# ARM2toARM6Adapter.net
KiCad netlist of a schematic drawn in Altium Designer
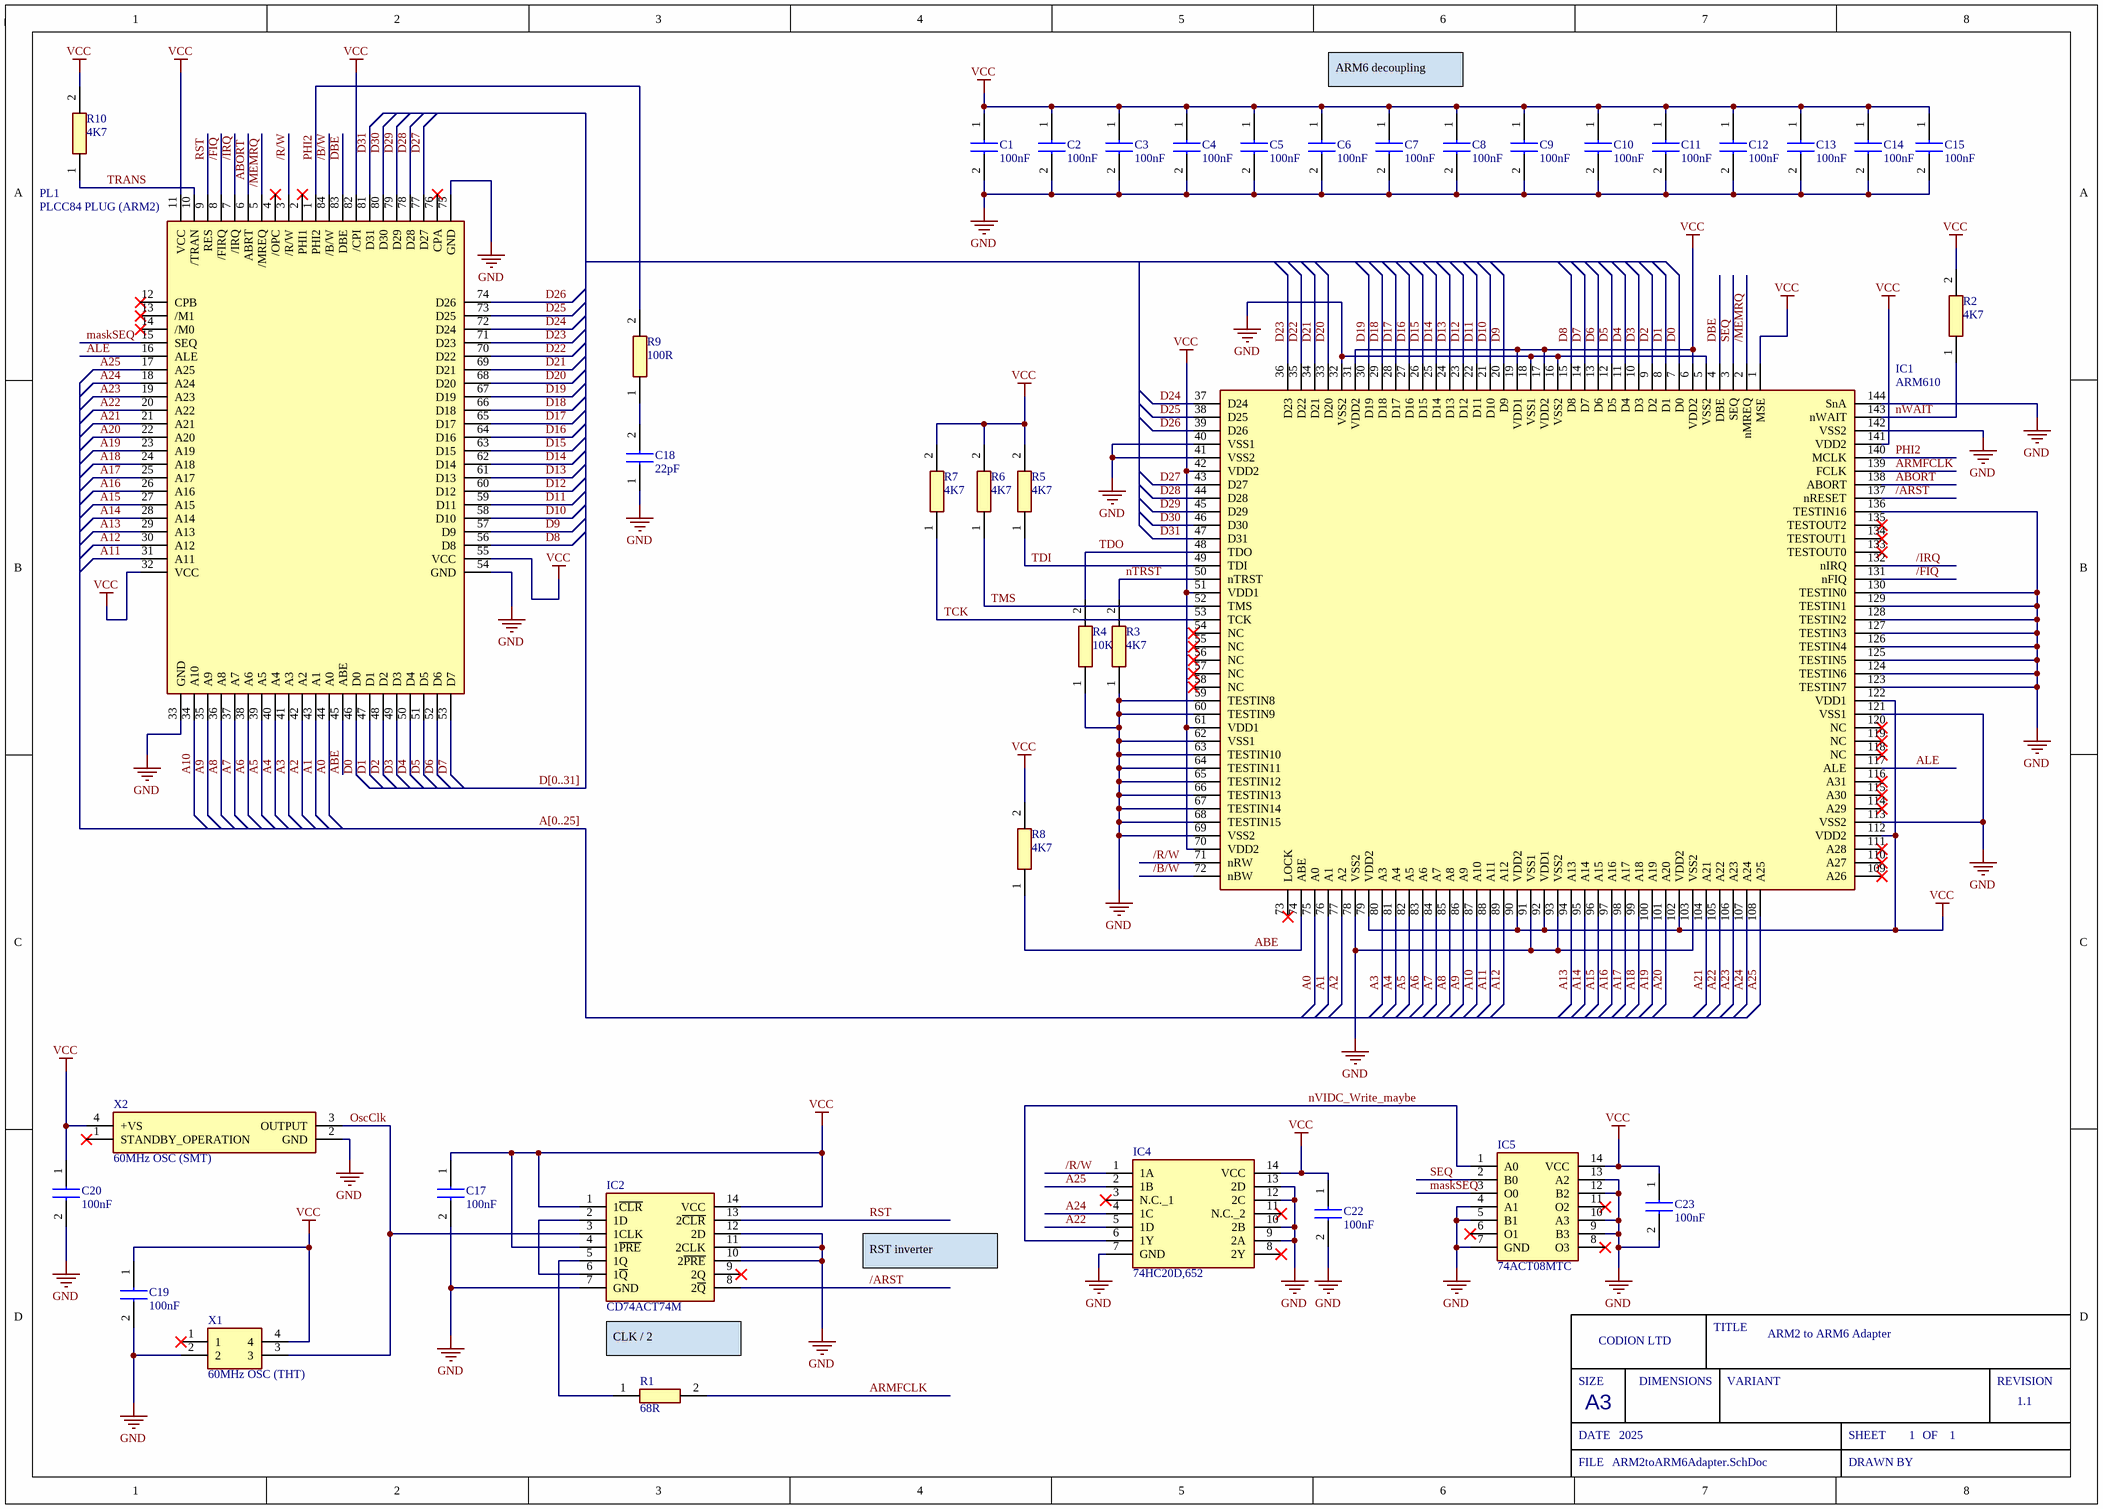
[diagram p0: ARM2toARM6Adapter.SchDoc]

(export (version "E")
  (design (tool "Eeschema 10.0.6"))
  (components
    (comp (ref "C1")
      (value "100nF")
      (footprint "SamacSys:CAPC2012X145N")
      (description "Capacitor")
      (fields
        (field (name "MANUFACTURER_PART_NUMBER") "C2012X7R1H104K125AM")
        (field (name "MOUSER PART NUMBER") "810-C2012X7R1H104KT5")
      )
      (libsource (lib "*") (part "C2012X7R1H104K125AM"))
    )
    (comp (ref "C2")
      (value "100nF")
      (footprint "SamacSys:CAPC2012X145N")
      (description "Capacitor")
      (fields
        (field (name "MANUFACTURER_PART_NUMBER") "C2012X7R1H104K125AM")
        (field (name "MOUSER PART NUMBER") "810-C2012X7R1H104KT5")
      )
      (libsource (lib "*") (part "C2012X7R1H104K125AM"))
    )
    (comp (ref "C3")
      (value "100nF")
      (footprint "SamacSys:CAPC2012X145N")
      (description "Capacitor")
      (fields
        (field (name "MANUFACTURER_PART_NUMBER") "C2012X7R1H104K125AM")
        (field (name "MOUSER PART NUMBER") "810-C2012X7R1H104KT5")
      )
      (libsource (lib "*") (part "C2012X7R1H104K125AM"))
    )
    (comp (ref "C4")
      (value "100nF")
      (footprint "SamacSys:CAPC2012X145N")
      (description "Capacitor")
      (fields
        (field (name "MANUFACTURER_PART_NUMBER") "C2012X7R1H104K125AM")
        (field (name "MOUSER PART NUMBER") "810-C2012X7R1H104KT5")
      )
      (libsource (lib "*") (part "C2012X7R1H104K125AM"))
    )
    (comp (ref "C5")
      (value "100nF")
      (footprint "SamacSys:CAPC2012X145N")
      (description "Capacitor")
      (fields
        (field (name "MANUFACTURER_PART_NUMBER") "C2012X7R1H104K125AM")
        (field (name "MOUSER PART NUMBER") "810-C2012X7R1H104KT5")
      )
      (libsource (lib "*") (part "C2012X7R1H104K125AM"))
    )
    (comp (ref "C6")
      (value "100nF")
      (footprint "SamacSys:CAPC2012X145N")
      (description "Capacitor")
      (fields
        (field (name "MANUFACTURER_PART_NUMBER") "C2012X7R1H104K125AM")
        (field (name "MOUSER PART NUMBER") "810-C2012X7R1H104KT5")
      )
      (libsource (lib "*") (part "C2012X7R1H104K125AM"))
    )
    (comp (ref "C7")
      (value "100nF")
      (footprint "SamacSys:CAPC2012X145N")
      (description "Capacitor")
      (fields
        (field (name "MANUFACTURER_PART_NUMBER") "C2012X7R1H104K125AM")
        (field (name "MOUSER PART NUMBER") "810-C2012X7R1H104KT5")
      )
      (libsource (lib "*") (part "C2012X7R1H104K125AM"))
    )
    (comp (ref "C8")
      (value "100nF")
      (footprint "SamacSys:CAPC2012X145N")
      (description "Capacitor")
      (fields
        (field (name "MANUFACTURER_PART_NUMBER") "C2012X7R1H104K125AM")
        (field (name "MOUSER PART NUMBER") "810-C2012X7R1H104KT5")
      )
      (libsource (lib "*") (part "C2012X7R1H104K125AM"))
    )
    (comp (ref "C9")
      (value "100nF")
      (footprint "SamacSys:CAPC2012X145N")
      (description "Capacitor")
      (fields
        (field (name "MANUFACTURER_PART_NUMBER") "C2012X7R1H104K125AM")
        (field (name "MOUSER PART NUMBER") "810-C2012X7R1H104KT5")
      )
      (libsource (lib "*") (part "C2012X7R1H104K125AM"))
    )
    (comp (ref "C10")
      (value "100nF")
      (footprint "SamacSys:CAPC2012X145N")
      (description "Capacitor")
      (fields
        (field (name "MANUFACTURER_PART_NUMBER") "C2012X7R1H104K125AM")
        (field (name "MOUSER PART NUMBER") "810-C2012X7R1H104KT5")
      )
      (libsource (lib "*") (part "C2012X7R1H104K125AM"))
    )
    (comp (ref "C11")
      (value "100nF")
      (footprint "SamacSys:CAPC2012X145N")
      (description "Capacitor")
      (fields
        (field (name "MANUFACTURER_PART_NUMBER") "C2012X7R1H104K125AM")
        (field (name "MOUSER PART NUMBER") "810-C2012X7R1H104KT5")
      )
      (libsource (lib "*") (part "C2012X7R1H104K125AM"))
    )
    (comp (ref "C12")
      (value "100nF")
      (footprint "SamacSys:CAPC2012X145N")
      (description "Capacitor")
      (fields
        (field (name "MANUFACTURER_PART_NUMBER") "C2012X7R1H104K125AM")
        (field (name "MOUSER PART NUMBER") "810-C2012X7R1H104KT5")
      )
      (libsource (lib "*") (part "C2012X7R1H104K125AM"))
    )
    (comp (ref "C13")
      (value "100nF")
      (footprint "SamacSys:CAPC2012X145N")
      (description "Capacitor")
      (fields
        (field (name "MANUFACTURER_PART_NUMBER") "C2012X7R1H104K125AM")
        (field (name "MOUSER PART NUMBER") "810-C2012X7R1H104KT5")
      )
      (libsource (lib "*") (part "C2012X7R1H104K125AM"))
    )
    (comp (ref "C14")
      (value "100nF")
      (footprint "SamacSys:CAPC2012X145N")
      (description "Capacitor")
      (fields
        (field (name "MANUFACTURER_PART_NUMBER") "C2012X7R1H104K125AM")
        (field (name "MOUSER PART NUMBER") "810-C2012X7R1H104KT5")
      )
      (libsource (lib "*") (part "C2012X7R1H104K125AM"))
    )
    (comp (ref "C15")
      (value "100nF")
      (footprint "SamacSys:CAPC2012X145N")
      (description "Capacitor")
      (fields
        (field (name "MANUFACTURER_PART_NUMBER") "C2012X7R1H104K125AM")
        (field (name "MOUSER PART NUMBER") "810-C2012X7R1H104KT5")
      )
      (libsource (lib "*") (part "C2012X7R1H104K125AM"))
    )
    (comp (ref "C17")
      (value "100nF")
      (footprint "SamacSys:CAPC2012X145N")
      (description "Capacitor")
      (fields
        (field (name "MANUFACTURER_PART_NUMBER") "C2012X7R1H104K125AM")
        (field (name "MOUSER PART NUMBER") "810-C2012X7R1H104KT5")
      )
      (libsource (lib "*") (part "C2012X7R1H104K125AM"))
    )
    (comp (ref "C18")
      (value "22pF")
      (footprint "SamacSys:CAPC1608X90N")
      (description "Capacitor")
      (fields
        (field (name "MANUFACTURER_PART_NUMBER") "CGA3E2NP02A220J080AA")
        (field (name "MOUSER PART NUMBER") "810-CGA3E2NP02A220JA")
      )
      (libsource (lib "*") (part "CGA3E2NP02A220J080AA"))
    )
    (comp (ref "C19")
      (value "100nF")
      (footprint "SamacSys:CAPC2012X145N")
      (description "Capacitor")
      (fields
        (field (name "MANUFACTURER_PART_NUMBER") "C2012X7R1H104K125AM")
        (field (name "MOUSER PART NUMBER") "810-C2012X7R1H104KT5")
      )
      (libsource (lib "*") (part "C2012X7R1H104K125AM"))
    )
    (comp (ref "C20")
      (value "100nF")
      (footprint "SamacSys:CAPC2012X145N")
      (description "Capacitor")
      (fields
        (field (name "MANUFACTURER_PART_NUMBER") "C2012X7R1H104K125AM")
        (field (name "MOUSER PART NUMBER") "810-C2012X7R1H104KT5")
      )
      (libsource (lib "*") (part "C2012X7R1H104K125AM"))
    )
    (comp (ref "C22")
      (value "100nF")
      (footprint "SamacSys:CAPC2012X145N")
      (description "Capacitor")
      (fields
        (field (name "MANUFACTURER_PART_NUMBER") "C2012X7R1H104K125AM")
        (field (name "MOUSER PART NUMBER") "810-C2012X7R1H104KT5")
      )
      (libsource (lib "*") (part "C2012X7R1H104K125AM"))
    )
    (comp (ref "C23")
      (value "100nF")
      (footprint "SamacSys:CAPC2012X145N")
      (description "Capacitor")
      (fields
        (field (name "MANUFACTURER_PART_NUMBER") "C2012X7R1H104K125AM")
        (field (name "MOUSER PART NUMBER") "810-C2012X7R1H104KT5")
      )
      (libsource (lib "*") (part "C2012X7R1H104K125AM"))
    )
    (comp (ref "IC1")
      (value "ARM610")
      (footprint "PcbLib1:TQFP144")
      (fields (field (name "MANUFACTURER_PART_NUMBER") "VY86C610C"))
      (libsource (lib "Schlib1") (part "VY86C610"))
    )
    (comp (ref "IC2")
      (value "CD74ACT74M")
      (footprint "SamacSys:SOIC127P600X175-14N")
      (description "Integrated Circuit")
      (fields (field (name "MOUSER PART NUMBER") "595-CD74ACT74M"))
      (libsource (lib "*") (part "CD74ACT74M"))
    )
    (comp (ref "IC4")
      (value "74HC20D,652")
      (footprint "SamacSys:SOIC127P600X175-14N")
      (description "Integrated Circuit")
      (fields (field (name "MOUSER PART NUMBER") "771-74HC20D"))
      (libsource (lib "*") (part "74HC20D,652"))
    )
    (comp (ref "IC5")
      (value "74ACT08MTC")
      (footprint "SamacSys:SOIC127P600X175-14N")
      (description "Integrated Circuit")
      (fields (field (name "MOUSER PART NUMBER") "512-74ACT08MTC"))
      (libsource (lib "SamacSys") (part "74ACT08MTC"))
    )
    (comp (ref "PL1")
      (value "PLCC84 PLUG (ARM2)")
      (footprint "PLCC84_PLUG")
      (description "PLCC84 Plug")
      (fields (field (name "MANUFACTURER_PART_NUMBER") "W9328"))
      (libsource (lib "ARM2toARM3Adapter") (part "PLCC84_PLUG_ARM2"))
    )
    (comp (ref "R1")
      (value "68R")
      (footprint "SamacSys:RESC2012X50N")
      (description "68R Resistor")
      (fields
        (field (name "MANUFACTURER_PART_NUMBER") "CRCW080568R0FKEA")
        (field (name "MOUSER PART NUMBER") "71-CRCW080568R0FKEA")
      )
      (libsource (lib "*") (part "CRCW080568R0FKEA"))
    )
    (comp (ref "R2")
      (value "4K7")
      (footprint "SamacSys:RESC1005X35N")
      (description "Resistor")
      (fields
        (field (name "MANUFACTURER_PART_NUMBER") "CPF0402B4K75E1")
        (field (name "MOUSER PART NUMBER") "279-CPF0402B4K75E1")
      )
      (libsource (lib "*") (part "CPF0402B4K75E1"))
    )
    (comp (ref "R3")
      (value "4K7")
      (footprint "SamacSys:RESC1005X35N")
      (description "Resistor")
      (fields
        (field (name "MANUFACTURER_PART_NUMBER") "CPF0402B4K75E1")
        (field (name "MOUSER PART NUMBER") "279-CPF0402B4K75E1")
      )
      (libsource (lib "*") (part "CPF0402B4K75E1"))
    )
    (comp (ref "R4")
      (value "10K")
      (footprint "SamacSys:RESC1005X35N")
      (description "Resistor")
      (fields (field (name "MANUFACTURER_PART_NUMBER") "CPF0402B10K5E"))
      (libsource (lib "*") (part "CPF0402B10K5E"))
    )
    (comp (ref "R5")
      (value "4K7")
      (footprint "SamacSys:RESC1005X35N")
      (description "Resistor")
      (fields
        (field (name "MANUFACTURER_PART_NUMBER") "CPF0402B4K75E1")
        (field (name "MOUSER PART NUMBER") "279-CPF0402B4K75E1")
      )
      (libsource (lib "*") (part "CPF0402B4K75E1"))
    )
    (comp (ref "R6")
      (value "4K7")
      (footprint "SamacSys:RESC1005X35N")
      (description "Resistor")
      (fields
        (field (name "MANUFACTURER_PART_NUMBER") "CPF0402B4K75E1")
        (field (name "MOUSER PART NUMBER") "279-CPF0402B4K75E1")
      )
      (libsource (lib "*") (part "CPF0402B4K75E1"))
    )
    (comp (ref "R7")
      (value "4K7")
      (footprint "SamacSys:RESC1005X35N")
      (description "Resistor")
      (fields
        (field (name "MANUFACTURER_PART_NUMBER") "CPF0402B4K75E1")
        (field (name "MOUSER PART NUMBER") "279-CPF0402B4K75E1")
      )
      (libsource (lib "*") (part "CPF0402B4K75E1"))
    )
    (comp (ref "R8")
      (value "4K7")
      (footprint "SamacSys:RESC1005X35N")
      (description "Resistor")
      (fields
        (field (name "MANUFACTURER_PART_NUMBER") "CPF0402B4K75E1")
        (field (name "MOUSER PART NUMBER") "279-CPF0402B4K75E1")
      )
      (libsource (lib "*") (part "CPF0402B4K75E1"))
    )
    (comp (ref "R9")
      (value "100R")
      (footprint "SamacSys:RESC2012X60N")
      (description "Resistor")
      (fields
        (field (name "MANUFACTURER_PART_NUMBER") "CRCW0805100RFKEAC")
        (field (name "MOUSER PART NUMBER") "71-CRCW0805100RFKEAC")
      )
      (libsource (lib "*") (part "CRCW0805100RFKEAC"))
    )
    (comp (ref "R10")
      (value "4K7")
      (footprint "SamacSys:RESC1005X35N")
      (description "Resistor")
      (fields
        (field (name "MANUFACTURER_PART_NUMBER") "CPF0402B4K75E1")
        (field (name "MOUSER PART NUMBER") "279-CPF0402B4K75E1")
      )
      (libsource (lib "*") (part "CPF0402B4K75E1"))
    )
    (comp (ref "X1")
      (value "60MHz OSC (THT)")
      (footprint "SamacSys:DIPS762W56P1524L1778H241Q4N")
      (description "60MHz OSC")
      (fields
        (field (name "MANUFACTURER_PART_NUMBER") "1107741")
        (field (name "MOUSER PART NUMBER") "535-1107741")
      )
      (libsource (lib "*") (part "1107741"))
    )
    (comp (ref "X2")
      (value "60MHz OSC (SMT)")
      (footprint "SamacSys:LFSPXO018035Bulk")
      (description "Crystal or Oscillator")
      (fields
        (field (name "MANUFACTURER_PART_NUMBER") "LFSPXO018035Bulk")
        (field (name "MOUSER PART NUMBER") "449-LFSPXO018035BULK")
      )
      (libsource (lib "*") (part "LFSPXO018035Bulk"))
    )
  )
  (nets
    (net (code "1") (name "/A0") (class "Default")
      (node (ref "IC1") (pin "75") (pinfunction "A0_75") (pintype "passive"))
      (node (ref "PL1") (pin "44") (pinfunction "A0_44") (pintype "passive"))
    )
    (net (code "2") (name "/A1") (class "Default")
      (node (ref "IC1") (pin "76") (pinfunction "A1_76") (pintype "passive"))
      (node (ref "PL1") (pin "43") (pinfunction "A1_43") (pintype "passive"))
    )
    (net (code "3") (name "/A2") (class "Default")
      (node (ref "IC1") (pin "77") (pinfunction "A2_77") (pintype "passive"))
      (node (ref "PL1") (pin "42") (pinfunction "A2_42") (pintype "passive"))
    )
    (net (code "4") (name "/A3") (class "Default")
      (node (ref "IC1") (pin "80") (pinfunction "A3_80") (pintype "passive"))
      (node (ref "PL1") (pin "41") (pinfunction "A3_41") (pintype "passive"))
    )
    (net (code "5") (name "/A4") (class "Default")
      (node (ref "IC1") (pin "81") (pinfunction "A4_81") (pintype "passive"))
      (node (ref "PL1") (pin "40") (pinfunction "A4_40") (pintype "passive"))
    )
    (net (code "6") (name "/A5") (class "Default")
      (node (ref "IC1") (pin "82") (pinfunction "A5_82") (pintype "passive"))
      (node (ref "PL1") (pin "39") (pinfunction "A5_39") (pintype "passive"))
    )
    (net (code "7") (name "/A6") (class "Default")
      (node (ref "IC1") (pin "83") (pinfunction "A6_83") (pintype "passive"))
      (node (ref "PL1") (pin "38") (pinfunction "A6_38") (pintype "passive"))
    )
    (net (code "8") (name "/A7") (class "Default")
      (node (ref "IC1") (pin "84") (pinfunction "A7_84") (pintype "passive"))
      (node (ref "PL1") (pin "37") (pinfunction "A7_37") (pintype "passive"))
    )
    (net (code "9") (name "/A8") (class "Default")
      (node (ref "IC1") (pin "85") (pinfunction "A8_85") (pintype "passive"))
      (node (ref "PL1") (pin "36") (pinfunction "A8_36") (pintype "passive"))
    )
    (net (code "10") (name "/A9") (class "Default")
      (node (ref "IC1") (pin "86") (pinfunction "A9_86") (pintype "passive"))
      (node (ref "PL1") (pin "35") (pinfunction "A9_35") (pintype "passive"))
    )
    (net (code "11") (name "/A10") (class "Default")
      (node (ref "IC1") (pin "87") (pinfunction "A10_87") (pintype "passive"))
      (node (ref "PL1") (pin "34") (pinfunction "A10_34") (pintype "passive"))
    )
    (net (code "12") (name "/A11") (class "Default")
      (node (ref "IC1") (pin "88") (pinfunction "A11_88") (pintype "passive"))
      (node (ref "PL1") (pin "31") (pinfunction "A11_31") (pintype "passive"))
    )
    (net (code "13") (name "/A12") (class "Default")
      (node (ref "IC1") (pin "89") (pinfunction "A12_89") (pintype "passive"))
      (node (ref "PL1") (pin "30") (pinfunction "A12_30") (pintype "passive"))
    )
    (net (code "14") (name "/A13") (class "Default")
      (node (ref "IC1") (pin "94") (pinfunction "A13_94") (pintype "passive"))
      (node (ref "PL1") (pin "29") (pinfunction "A13_29") (pintype "passive"))
    )
    (net (code "15") (name "/A14") (class "Default")
      (node (ref "IC1") (pin "95") (pinfunction "A14_95") (pintype "passive"))
      (node (ref "PL1") (pin "28") (pinfunction "A14_28") (pintype "passive"))
    )
    (net (code "16") (name "/A15") (class "Default")
      (node (ref "IC1") (pin "96") (pinfunction "A15_96") (pintype "passive"))
      (node (ref "PL1") (pin "27") (pinfunction "A15_27") (pintype "passive"))
    )
    (net (code "17") (name "/A16") (class "Default")
      (node (ref "IC1") (pin "97") (pinfunction "A16_97") (pintype "passive"))
      (node (ref "PL1") (pin "26") (pinfunction "A16_26") (pintype "passive"))
    )
    (net (code "18") (name "/A17") (class "Default")
      (node (ref "IC1") (pin "98") (pinfunction "A17_98") (pintype "passive"))
      (node (ref "PL1") (pin "25") (pinfunction "A17_25") (pintype "passive"))
    )
    (net (code "19") (name "/A18") (class "Default")
      (node (ref "IC1") (pin "99") (pinfunction "A18_99") (pintype "passive"))
      (node (ref "PL1") (pin "24") (pinfunction "A18_24") (pintype "passive"))
    )
    (net (code "20") (name "/A19") (class "Default")
      (node (ref "IC1") (pin "100") (pinfunction "A19_100") (pintype "passive"))
      (node (ref "PL1") (pin "23") (pinfunction "A19_23") (pintype "passive"))
    )
    (net (code "21") (name "/A20") (class "Default")
      (node (ref "IC1") (pin "101") (pinfunction "A20_101") (pintype "passive"))
      (node (ref "PL1") (pin "22") (pinfunction "A20_22") (pintype "passive"))
    )
    (net (code "22") (name "/A21") (class "Default")
      (node (ref "IC1") (pin "104") (pinfunction "A21_104") (pintype "passive"))
      (node (ref "PL1") (pin "21") (pinfunction "A21_21") (pintype "passive"))
    )
    (net (code "23") (name "/A22") (class "Default")
      (node (ref "IC1") (pin "105") (pinfunction "A22_105") (pintype "passive"))
      (node (ref "IC4") (pin "5") (pinfunction "1D_5") (pintype "passive"))
      (node (ref "PL1") (pin "20") (pinfunction "A22_20") (pintype "passive"))
    )
    (net (code "24") (name "/A23") (class "Default")
      (node (ref "IC1") (pin "106") (pinfunction "A23_106") (pintype "passive"))
      (node (ref "PL1") (pin "19") (pinfunction "A23_19") (pintype "passive"))
    )
    (net (code "25") (name "/A24") (class "Default")
      (node (ref "IC1") (pin "107") (pinfunction "A24_107") (pintype "passive"))
      (node (ref "IC4") (pin "4") (pinfunction "1C_4") (pintype "passive"))
      (node (ref "PL1") (pin "18") (pinfunction "A24_18") (pintype "passive"))
    )
    (net (code "26") (name "/A25") (class "Default")
      (node (ref "IC1") (pin "108") (pinfunction "A25_108") (pintype "passive"))
      (node (ref "IC4") (pin "2") (pinfunction "1B_2") (pintype "passive"))
      (node (ref "PL1") (pin "17") (pinfunction "A25_17") (pintype "passive"))
    )
    (net (code "27") (name "/ABE") (class "Default")
      (node (ref "IC1") (pin "74") (pinfunction "ABE_74") (pintype "passive"))
      (node (ref "PL1") (pin "45") (pinfunction "ABE_45") (pintype "passive"))
      (node (ref "R8") (pin "1") (pinfunction "1_1") (pintype "passive"))
    )
    (net (code "28") (name "/ABORT") (class "Default")
      (node (ref "IC1") (pin "138") (pinfunction "ABORT_138") (pintype "passive"))
      (node (ref "PL1") (pin "6") (pinfunction "ABRT_6") (pintype "passive"))
    )
    (net (code "29") (name "/ALE") (class "Default")
      (node (ref "IC1") (pin "117") (pinfunction "ALE_117") (pintype "passive"))
      (node (ref "PL1") (pin "16") (pinfunction "ALE_16") (pintype "passive"))
    )
    (net (code "30") (name "/ARMFCLK") (class "Default")
      (node (ref "IC1") (pin "139") (pinfunction "FCLK_139") (pintype "passive"))
      (node (ref "R1") (pin "2") (pinfunction "2_2") (pintype "passive"))
    )
    (net (code "32") (name "/D0") (class "Default")
      (node (ref "IC1") (pin "7") (pinfunction "D0_7") (pintype "passive"))
      (node (ref "PL1") (pin "46") (pinfunction "D0_46") (pintype "passive"))
    )
    (net (code "33") (name "/D1") (class "Default")
      (node (ref "IC1") (pin "8") (pinfunction "D1_8") (pintype "passive"))
      (node (ref "PL1") (pin "47") (pinfunction "D1_47") (pintype "passive"))
    )
    (net (code "34") (name "/D2") (class "Default")
      (node (ref "IC1") (pin "9") (pinfunction "D2_9") (pintype "passive"))
      (node (ref "PL1") (pin "48") (pinfunction "D2_48") (pintype "passive"))
    )
    (net (code "35") (name "/D3") (class "Default")
      (node (ref "IC1") (pin "10") (pinfunction "D3_10") (pintype "passive"))
      (node (ref "PL1") (pin "49") (pinfunction "D3_49") (pintype "passive"))
    )
    (net (code "36") (name "/D4") (class "Default")
      (node (ref "IC1") (pin "11") (pinfunction "D4_11") (pintype "passive"))
      (node (ref "PL1") (pin "50") (pinfunction "D4_50") (pintype "passive"))
    )
    (net (code "37") (name "/D5") (class "Default")
      (node (ref "IC1") (pin "12") (pinfunction "D5_12") (pintype "passive"))
      (node (ref "PL1") (pin "51") (pinfunction "D5_51") (pintype "passive"))
    )
    (net (code "38") (name "/D6") (class "Default")
      (node (ref "IC1") (pin "13") (pinfunction "D6_13") (pintype "passive"))
      (node (ref "PL1") (pin "52") (pinfunction "D6_52") (pintype "passive"))
    )
    (net (code "39") (name "/D7") (class "Default")
      (node (ref "IC1") (pin "14") (pinfunction "D7_14") (pintype "passive"))
      (node (ref "PL1") (pin "53") (pinfunction "D7_53") (pintype "passive"))
    )
    (net (code "40") (name "/D8") (class "Default")
      (node (ref "IC1") (pin "15") (pinfunction "D8_15") (pintype "passive"))
      (node (ref "PL1") (pin "56") (pinfunction "D8_56") (pintype "passive"))
    )
    (net (code "41") (name "/D9") (class "Default")
      (node (ref "IC1") (pin "20") (pinfunction "D9_20") (pintype "passive"))
      (node (ref "PL1") (pin "57") (pinfunction "D9_57") (pintype "passive"))
    )
    (net (code "42") (name "/D10") (class "Default")
      (node (ref "IC1") (pin "21") (pinfunction "D10_21") (pintype "passive"))
      (node (ref "PL1") (pin "58") (pinfunction "D10_58") (pintype "passive"))
    )
    (net (code "43") (name "/D11") (class "Default")
      (node (ref "IC1") (pin "22") (pinfunction "D11_22") (pintype "passive"))
      (node (ref "PL1") (pin "59") (pinfunction "D11_59") (pintype "passive"))
    )
    (net (code "44") (name "/D12") (class "Default")
      (node (ref "IC1") (pin "23") (pinfunction "D12_23") (pintype "passive"))
      (node (ref "PL1") (pin "60") (pinfunction "D12_60") (pintype "passive"))
    )
    (net (code "45") (name "/D13") (class "Default")
      (node (ref "IC1") (pin "24") (pinfunction "D13_24") (pintype "passive"))
      (node (ref "PL1") (pin "61") (pinfunction "D13_61") (pintype "passive"))
    )
    (net (code "46") (name "/D14") (class "Default")
      (node (ref "IC1") (pin "25") (pinfunction "D14_25") (pintype "passive"))
      (node (ref "PL1") (pin "62") (pinfunction "D14_62") (pintype "passive"))
    )
    (net (code "47") (name "/D15") (class "Default")
      (node (ref "IC1") (pin "26") (pinfunction "D15_26") (pintype "passive"))
      (node (ref "PL1") (pin "63") (pinfunction "D15_63") (pintype "passive"))
    )
    (net (code "48") (name "/D16") (class "Default")
      (node (ref "IC1") (pin "27") (pinfunction "D16_27") (pintype "passive"))
      (node (ref "PL1") (pin "64") (pinfunction "D16_64") (pintype "passive"))
    )
    (net (code "49") (name "/D17") (class "Default")
      (node (ref "IC1") (pin "28") (pinfunction "D17_28") (pintype "passive"))
      (node (ref "PL1") (pin "65") (pinfunction "D17_65") (pintype "passive"))
    )
    (net (code "50") (name "/D18") (class "Default")
      (node (ref "IC1") (pin "29") (pinfunction "D18_29") (pintype "passive"))
      (node (ref "PL1") (pin "66") (pinfunction "D18_66") (pintype "passive"))
    )
    (net (code "51") (name "/D19") (class "Default")
      (node (ref "IC1") (pin "30") (pinfunction "D19_30") (pintype "passive"))
      (node (ref "PL1") (pin "67") (pinfunction "D19_67") (pintype "passive"))
    )
    (net (code "52") (name "/D20") (class "Default")
      (node (ref "IC1") (pin "33") (pinfunction "D20_33") (pintype "passive"))
      (node (ref "PL1") (pin "68") (pinfunction "D20_68") (pintype "passive"))
    )
    (net (code "53") (name "/D21") (class "Default")
      (node (ref "IC1") (pin "34") (pinfunction "D21_34") (pintype "passive"))
      (node (ref "PL1") (pin "69") (pinfunction "D21_69") (pintype "passive"))
    )
    (net (code "54") (name "/D22") (class "Default")
      (node (ref "IC1") (pin "35") (pinfunction "D22_35") (pintype "passive"))
      (node (ref "PL1") (pin "70") (pinfunction "D22_70") (pintype "passive"))
    )
    (net (code "55") (name "/D23") (class "Default")
      (node (ref "IC1") (pin "36") (pinfunction "D23_36") (pintype "passive"))
      (node (ref "PL1") (pin "71") (pinfunction "D23_71") (pintype "passive"))
    )
    (net (code "56") (name "/D24") (class "Default")
      (node (ref "IC1") (pin "37") (pinfunction "D24_37") (pintype "passive"))
      (node (ref "PL1") (pin "72") (pinfunction "D24_72") (pintype "passive"))
    )
    (net (code "57") (name "/D25") (class "Default")
      (node (ref "IC1") (pin "38") (pinfunction "D25_38") (pintype "passive"))
      (node (ref "PL1") (pin "73") (pinfunction "D25_73") (pintype "passive"))
    )
    (net (code "58") (name "/D26") (class "Default")
      (node (ref "IC1") (pin "39") (pinfunction "D26_39") (pintype "passive"))
      (node (ref "PL1") (pin "74") (pinfunction "D26_74") (pintype "passive"))
    )
    (net (code "59") (name "/D27") (class "Default")
      (node (ref "IC1") (pin "43") (pinfunction "D27_43") (pintype "passive"))
      (node (ref "PL1") (pin "77") (pinfunction "D27_77") (pintype "passive"))
    )
    (net (code "60") (name "/D28") (class "Default")
      (node (ref "IC1") (pin "44") (pinfunction "D28_44") (pintype "passive"))
      (node (ref "PL1") (pin "78") (pinfunction "D28_78") (pintype "passive"))
    )
    (net (code "61") (name "/D29") (class "Default")
      (node (ref "IC1") (pin "45") (pinfunction "D29_45") (pintype "passive"))
      (node (ref "PL1") (pin "79") (pinfunction "D29_79") (pintype "passive"))
    )
    (net (code "62") (name "/D30") (class "Default")
      (node (ref "IC1") (pin "46") (pinfunction "D30_46") (pintype "passive"))
      (node (ref "PL1") (pin "80") (pinfunction "D30_80") (pintype "passive"))
    )
    (net (code "63") (name "/D31") (class "Default")
      (node (ref "IC1") (pin "47") (pinfunction "D31_47") (pintype "passive"))
      (node (ref "PL1") (pin "81") (pinfunction "D31_81") (pintype "passive"))
    )
    (net (code "64") (name "/DBE") (class "Default")
      (node (ref "IC1") (pin "4") (pinfunction "DBE_4") (pintype "passive"))
      (node (ref "PL1") (pin "83") (pinfunction "DBE_83") (pintype "passive"))
    )
    (net (code "66") (name "/OscClk") (class "Default")
      (node (ref "IC2") (pin "3") (pinfunction "1CLK_3") (pintype "passive"))
      (node (ref "X1") (pin "3") (pinfunction "3_3") (pintype "passive"))
      (node (ref "X2") (pin "3") (pinfunction "OUTPUT_3") (pintype "passive"))
    )
    (net (code "67") (name "/PHI2") (class "Default")
      (node (ref "IC1") (pin "140") (pinfunction "MCLK_140") (pintype "passive"))
      (node (ref "PL1") (pin "1") (pinfunction "PHI2_1") (pintype "passive"))
      (node (ref "R9") (pin "2") (pinfunction "2_2") (pintype "passive"))
    )
    (net (code "68") (name "/RST") (class "Default")
      (node (ref "IC2") (pin "13") (pinfunction "2~{CLR}_13") (pintype "passive"))
      (node (ref "PL1") (pin "9") (pinfunction "RES_9") (pintype "passive"))
    )
    (net (code "69") (name "/SEQ") (class "Default")
      (node (ref "IC1") (pin "3") (pinfunction "SEQ_3") (pintype "passive"))
      (node (ref "IC5") (pin "2") (pinfunction "B0_2") (pintype "passive"))
    )
    (net (code "70") (name "/TCK") (class "Default")
      (node (ref "IC1") (pin "53") (pinfunction "TCK_53") (pintype "passive"))
      (node (ref "R7") (pin "1") (pinfunction "1_1") (pintype "passive"))
    )
    (net (code "71") (name "/TDI") (class "Default")
      (node (ref "IC1") (pin "49") (pinfunction "TDI_49") (pintype "passive"))
      (node (ref "R5") (pin "1") (pinfunction "1_1") (pintype "passive"))
    )
    (net (code "72") (name "/TDO") (class "Default")
      (node (ref "IC1") (pin "48") (pinfunction "TDO_48") (pintype "passive"))
      (node (ref "R4") (pin "2") (pinfunction "2_2") (pintype "passive"))
    )
    (net (code "73") (name "/TMS") (class "Default")
      (node (ref "IC1") (pin "52") (pinfunction "TMS_52") (pintype "passive"))
      (node (ref "R6") (pin "1") (pinfunction "1_1") (pintype "passive"))
    )
    (net (code "74") (name "/TRANS") (class "Default")
      (node (ref "PL1") (pin "10") (pinfunction "/TRAN_10") (pintype "passive"))
      (node (ref "R10") (pin "1") (pinfunction "1_1") (pintype "passive"))
    )
    (net (code "75") (name "/maskSEQ") (class "Default")
      (node (ref "IC5") (pin "3") (pinfunction "O0_3") (pintype "passive"))
      (node (ref "PL1") (pin "15") (pinfunction "SEQ_15") (pintype "passive"))
    )
    (net (code "76") (name "/nTRST") (class "Default")
      (node (ref "IC1") (pin "50") (pinfunction "nTRST_50") (pintype "passive"))
      (node (ref "R3") (pin "2") (pinfunction "2_2") (pintype "passive"))
    )
    (net (code "77") (name "/nVIDC_Write_maybe") (class "Default")
      (node (ref "IC4") (pin "6") (pinfunction "1Y_6") (pintype "passive"))
      (node (ref "IC5") (pin "1") (pinfunction "A0_1") (pintype "passive"))
    )
    (net (code "78") (name "/nWAIT") (class "Default")
      (node (ref "IC1") (pin "143") (pinfunction "nWAIT_143") (pintype "passive"))
      (node (ref "R2") (pin "1") (pinfunction "1_1") (pintype "passive"))
    )
    (net (code "79") (name "/{slash}ARST") (class "Default")
      (node (ref "IC1") (pin "137") (pinfunction "nRESET_137") (pintype "passive"))
      (node (ref "IC2") (pin "8") (pinfunction "2~{Q}_8") (pintype "passive"))
    )
    (net (code "80") (name "/{slash}B{slash}W") (class "Default")
      (node (ref "IC1") (pin "72") (pinfunction "nBW_72") (pintype "passive"))
      (node (ref "PL1") (pin "84") (pinfunction "/B/W_84") (pintype "passive"))
    )
    (net (code "81") (name "/{slash}FIQ") (class "Default")
      (node (ref "IC1") (pin "131") (pinfunction "nFIQ_131") (pintype "passive"))
      (node (ref "PL1") (pin "8") (pinfunction "/FIRQ_8") (pintype "passive"))
    )
    (net (code "82") (name "/{slash}IRQ") (class "Default")
      (node (ref "IC1") (pin "132") (pinfunction "nIRQ_132") (pintype "passive"))
      (node (ref "PL1") (pin "7") (pinfunction "/IRQ_7") (pintype "passive"))
    )
    (net (code "83") (name "/{slash}MEMRQ") (class "Default")
      (node (ref "IC1") (pin "2") (pinfunction "nMREQ_2") (pintype "passive"))
      (node (ref "PL1") (pin "5") (pinfunction "/MREQ_5") (pintype "passive"))
    )
    (net (code "84") (name "/{slash}R{slash}W") (class "Default")
      (node (ref "IC1") (pin "71") (pinfunction "nRW_71") (pintype "passive"))
      (node (ref "IC4") (pin "1") (pinfunction "1A_1") (pintype "passive"))
      (node (ref "PL1") (pin "3") (pinfunction "/R/W_3") (pintype "passive"))
    )
    (net (code "85") (name "GND") (class "Default")
      (node (ref "C1") (pin "2") (pinfunction "2_2") (pintype "passive"))
      (node (ref "C10") (pin "2") (pinfunction "2_2") (pintype "passive"))
      (node (ref "C11") (pin "2") (pinfunction "2_2") (pintype "passive"))
      (node (ref "C12") (pin "2") (pinfunction "2_2") (pintype "passive"))
      (node (ref "C13") (pin "2") (pinfunction "2_2") (pintype "passive"))
      (node (ref "C14") (pin "2") (pinfunction "2_2") (pintype "passive"))
      (node (ref "C15") (pin "2") (pinfunction "2_2") (pintype "passive"))
      (node (ref "C17") (pin "2") (pinfunction "2_2") (pintype "passive"))
      (node (ref "C18") (pin "1") (pinfunction "1_1") (pintype "passive"))
      (node (ref "C19") (pin "2") (pinfunction "2_2") (pintype "passive"))
      (node (ref "C2") (pin "2") (pinfunction "2_2") (pintype "passive"))
      (node (ref "C20") (pin "2") (pinfunction "2_2") (pintype "passive"))
      (node (ref "C22") (pin "2") (pinfunction "2_2") (pintype "passive"))
      (node (ref "C23") (pin "2") (pinfunction "2_2") (pintype "passive"))
      (node (ref "C3") (pin "2") (pinfunction "2_2") (pintype "passive"))
      (node (ref "C4") (pin "2") (pinfunction "2_2") (pintype "passive"))
      (node (ref "C5") (pin "2") (pinfunction "2_2") (pintype "passive"))
      (node (ref "C6") (pin "2") (pinfunction "2_2") (pintype "passive"))
      (node (ref "C7") (pin "2") (pinfunction "2_2") (pintype "passive"))
      (node (ref "C8") (pin "2") (pinfunction "2_2") (pintype "passive"))
      (node (ref "C9") (pin "2") (pinfunction "2_2") (pintype "passive"))
      (node (ref "IC1") (pin "103") (pinfunction "VSS2_103") (pintype "passive"))
      (node (ref "IC1") (pin "113") (pinfunction "VSS2_113") (pintype "passive"))
      (node (ref "IC1") (pin "121") (pinfunction "VSS1_121") (pintype "passive"))
      (node (ref "IC1") (pin "123") (pinfunction "TESTIN7_123") (pintype "passive"))
      (node (ref "IC1") (pin "124") (pinfunction "TESTIN6_124") (pintype "passive"))
      (node (ref "IC1") (pin "125") (pinfunction "TESTIN5_125") (pintype "passive"))
      (node (ref "IC1") (pin "126") (pinfunction "TESTIN4_126") (pintype "passive"))
      (node (ref "IC1") (pin "127") (pinfunction "TESTIN3_127") (pintype "passive"))
      (node (ref "IC1") (pin "128") (pinfunction "TESTIN2_128") (pintype "passive"))
      (node (ref "IC1") (pin "129") (pinfunction "TESTIN1_129") (pintype "passive"))
      (node (ref "IC1") (pin "130") (pinfunction "TESTIN0_130") (pintype "passive"))
      (node (ref "IC1") (pin "136") (pinfunction "TESTIN16_136") (pintype "passive"))
      (node (ref "IC1") (pin "142") (pinfunction "VSS2_142") (pintype "passive"))
      (node (ref "IC1") (pin "144") (pinfunction "SnA_144") (pintype "passive"))
      (node (ref "IC1") (pin "16") (pinfunction "VSS2_16") (pintype "passive"))
      (node (ref "IC1") (pin "18") (pinfunction "VSS1_18") (pintype "passive"))
      (node (ref "IC1") (pin "32") (pinfunction "VSS2_32") (pintype "passive"))
      (node (ref "IC1") (pin "40") (pinfunction "VSS1_40") (pintype "passive"))
      (node (ref "IC1") (pin "41") (pinfunction "VSS2_41") (pintype "passive"))
      (node (ref "IC1") (pin "5") (pinfunction "VSS2_5") (pintype "passive"))
      (node (ref "IC1") (pin "59") (pinfunction "TESTIN8_59") (pintype "passive"))
      (node (ref "IC1") (pin "60") (pinfunction "TESTIN9_60") (pintype "passive"))
      (node (ref "IC1") (pin "62") (pinfunction "VSS1_62") (pintype "passive"))
      (node (ref "IC1") (pin "63") (pinfunction "TESTIN10_63") (pintype "passive"))
      (node (ref "IC1") (pin "64") (pinfunction "TESTIN11_64") (pintype "passive"))
      (node (ref "IC1") (pin "65") (pinfunction "TESTIN12_65") (pintype "passive"))
      (node (ref "IC1") (pin "66") (pinfunction "TESTIN13_66") (pintype "passive"))
      (node (ref "IC1") (pin "67") (pinfunction "TESTIN14_67") (pintype "passive"))
      (node (ref "IC1") (pin "68") (pinfunction "TESTIN15_68") (pintype "passive"))
      (node (ref "IC1") (pin "69") (pinfunction "VSS2_69") (pintype "passive"))
      (node (ref "IC1") (pin "78") (pinfunction "VSS2_78") (pintype "passive"))
      (node (ref "IC1") (pin "91") (pinfunction "VSS1_91") (pintype "passive"))
      (node (ref "IC1") (pin "93") (pinfunction "VSS2_93") (pintype "passive"))
      (node (ref "IC2") (pin "10") (pinfunction "2~{PRE}_10") (pintype "passive"))
      (node (ref "IC2") (pin "11") (pinfunction "2CLK_11") (pintype "passive"))
      (node (ref "IC2") (pin "12") (pinfunction "2D_12") (pintype "passive"))
      (node (ref "IC2") (pin "7") (pinfunction "GND_7") (pintype "passive"))
      (node (ref "IC4") (pin "10") (pinfunction "2B_10") (pintype "passive"))
      (node (ref "IC4") (pin "12") (pinfunction "2C_12") (pintype "passive"))
      (node (ref "IC4") (pin "13") (pinfunction "2D_13") (pintype "passive"))
      (node (ref "IC4") (pin "7") (pinfunction "GND_7") (pintype "passive"))
      (node (ref "IC4") (pin "9") (pinfunction "2A_9") (pintype "passive"))
      (node (ref "IC5") (pin "10") (pinfunction "A3_10") (pintype "passive"))
      (node (ref "IC5") (pin "12") (pinfunction "B2_12") (pintype "passive"))
      (node (ref "IC5") (pin "13") (pinfunction "A2_13") (pintype "passive"))
      (node (ref "IC5") (pin "4") (pinfunction "A1_4") (pintype "passive"))
      (node (ref "IC5") (pin "5") (pinfunction "B1_5") (pintype "passive"))
      (node (ref "IC5") (pin "7") (pinfunction "GND_7") (pintype "passive"))
      (node (ref "IC5") (pin "9") (pinfunction "B3_9") (pintype "passive"))
      (node (ref "PL1") (pin "33") (pinfunction "GND_33") (pintype "passive"))
      (node (ref "PL1") (pin "54") (pinfunction "GND_54") (pintype "passive"))
      (node (ref "PL1") (pin "75") (pinfunction "GND_75") (pintype "passive"))
      (node (ref "R3") (pin "1") (pinfunction "1_1") (pintype "passive"))
      (node (ref "R4") (pin "1") (pinfunction "1_1") (pintype "passive"))
      (node (ref "X1") (pin "2") (pinfunction "2_2") (pintype "passive"))
      (node (ref "X2") (pin "2") (pinfunction "GND_2") (pintype "passive"))
    )
    (net (code "86") (name "Net-(C18-Pad2)") (class "Default")
      (node (ref "C18") (pin "2") (pinfunction "2_2") (pintype "passive"))
      (node (ref "R9") (pin "1") (pinfunction "1_1") (pintype "passive"))
    )
    (net (code "87") (name "Net-(IC2-1D)") (class "Default")
      (node (ref "IC2") (pin "2") (pinfunction "1D_2") (pintype "passive"))
      (node (ref "IC2") (pin "6") (pinfunction "1~{Q}_6") (pintype "passive"))
    )
    (net (code "88") (name "Net-(IC2-1Q)") (class "Default")
      (node (ref "IC2") (pin "5") (pinfunction "1Q_5") (pintype "passive"))
      (node (ref "R1") (pin "1") (pinfunction "1_1") (pintype "passive"))
    )
    (net (code "89") (name "VCC") (class "Default")
      (node (ref "C1") (pin "1") (pinfunction "1_1") (pintype "passive"))
      (node (ref "C10") (pin "1") (pinfunction "1_1") (pintype "passive"))
      (node (ref "C11") (pin "1") (pinfunction "1_1") (pintype "passive"))
      (node (ref "C12") (pin "1") (pinfunction "1_1") (pintype "passive"))
      (node (ref "C13") (pin "1") (pinfunction "1_1") (pintype "passive"))
      (node (ref "C14") (pin "1") (pinfunction "1_1") (pintype "passive"))
      (node (ref "C15") (pin "1") (pinfunction "1_1") (pintype "passive"))
      (node (ref "C17") (pin "1") (pinfunction "1_1") (pintype "passive"))
      (node (ref "C19") (pin "1") (pinfunction "1_1") (pintype "passive"))
      (node (ref "C2") (pin "1") (pinfunction "1_1") (pintype "passive"))
      (node (ref "C20") (pin "1") (pinfunction "1_1") (pintype "passive"))
      (node (ref "C22") (pin "1") (pinfunction "1_1") (pintype "passive"))
      (node (ref "C23") (pin "1") (pinfunction "1_1") (pintype "passive"))
      (node (ref "C3") (pin "1") (pinfunction "1_1") (pintype "passive"))
      (node (ref "C4") (pin "1") (pinfunction "1_1") (pintype "passive"))
      (node (ref "C5") (pin "1") (pinfunction "1_1") (pintype "passive"))
      (node (ref "C6") (pin "1") (pinfunction "1_1") (pintype "passive"))
      (node (ref "C7") (pin "1") (pinfunction "1_1") (pintype "passive"))
      (node (ref "C8") (pin "1") (pinfunction "1_1") (pintype "passive"))
      (node (ref "C9") (pin "1") (pinfunction "1_1") (pintype "passive"))
      (node (ref "IC1") (pin "1") (pinfunction "MSE_1") (pintype "passive"))
      (node (ref "IC1") (pin "102") (pinfunction "VDD2_102") (pintype "passive"))
      (node (ref "IC1") (pin "112") (pinfunction "VDD2_112") (pintype "passive"))
      (node (ref "IC1") (pin "122") (pinfunction "VDD1_122") (pintype "passive"))
      (node (ref "IC1") (pin "141") (pinfunction "VDD2_141") (pintype "passive"))
      (node (ref "IC1") (pin "17") (pinfunction "VDD2_17") (pintype "passive"))
      (node (ref "IC1") (pin "19") (pinfunction "VDD1_19") (pintype "passive"))
      (node (ref "IC1") (pin "31") (pinfunction "VDD2_31") (pintype "passive"))
      (node (ref "IC1") (pin "42") (pinfunction "VDD2_42") (pintype "passive"))
      (node (ref "IC1") (pin "51") (pinfunction "VDD1_51") (pintype "passive"))
      (node (ref "IC1") (pin "6") (pinfunction "VDD2_6") (pintype "passive"))
      (node (ref "IC1") (pin "61") (pinfunction "VDD1_61") (pintype "passive"))
      (node (ref "IC1") (pin "70") (pinfunction "VDD2_70") (pintype "passive"))
      (node (ref "IC1") (pin "79") (pinfunction "VDD2_79") (pintype "passive"))
      (node (ref "IC1") (pin "90") (pinfunction "VDD2_90") (pintype "passive"))
      (node (ref "IC1") (pin "92") (pinfunction "VDD1_92") (pintype "passive"))
      (node (ref "IC2") (pin "1") (pinfunction "1~{CLR}_1") (pintype "passive"))
      (node (ref "IC2") (pin "14") (pinfunction "VCC_14") (pintype "passive"))
      (node (ref "IC2") (pin "4") (pinfunction "1~{PRE}_4") (pintype "passive"))
      (node (ref "IC4") (pin "14") (pinfunction "VCC_14") (pintype "passive"))
      (node (ref "IC5") (pin "14") (pinfunction "VCC_14") (pintype "passive"))
      (node (ref "PL1") (pin "11") (pinfunction "VCC_11") (pintype "passive"))
      (node (ref "PL1") (pin "32") (pinfunction "VCC_32") (pintype "passive"))
      (node (ref "PL1") (pin "55") (pinfunction "VCC_55") (pintype "passive"))
      (node (ref "PL1") (pin "82") (pinfunction "/CPI_82") (pintype "passive"))
      (node (ref "R10") (pin "2") (pinfunction "2_2") (pintype "passive"))
      (node (ref "R2") (pin "2") (pinfunction "2_2") (pintype "passive"))
      (node (ref "R5") (pin "2") (pinfunction "2_2") (pintype "passive"))
      (node (ref "R6") (pin "2") (pinfunction "2_2") (pintype "passive"))
      (node (ref "R7") (pin "2") (pinfunction "2_2") (pintype "passive"))
      (node (ref "R8") (pin "2") (pinfunction "2_2") (pintype "passive"))
      (node (ref "X1") (pin "4") (pinfunction "4_4") (pintype "passive"))
      (node (ref "X2") (pin "4") (pinfunction "+VS_4") (pintype "passive"))
    )
    (net (code "90") (name "unconnected-(IC1-A26-Pad109)") (class "Default")
      (node (ref "IC1") (pin "109") (pinfunction "A26_109") (pintype "passive+no_connect"))
    )
    (net (code "91") (name "unconnected-(IC1-A27-Pad110)") (class "Default")
      (node (ref "IC1") (pin "110") (pinfunction "A27_110") (pintype "passive+no_connect"))
    )
    (net (code "92") (name "unconnected-(IC1-A28-Pad111)") (class "Default")
      (node (ref "IC1") (pin "111") (pinfunction "A28_111") (pintype "passive+no_connect"))
    )
    (net (code "93") (name "unconnected-(IC1-A29-Pad114)") (class "Default")
      (node (ref "IC1") (pin "114") (pinfunction "A29_114") (pintype "passive+no_connect"))
    )
    (net (code "94") (name "unconnected-(IC1-A30-Pad115)") (class "Default")
      (node (ref "IC1") (pin "115") (pinfunction "A30_115") (pintype "passive+no_connect"))
    )
    (net (code "95") (name "unconnected-(IC1-A31-Pad116)") (class "Default")
      (node (ref "IC1") (pin "116") (pinfunction "A31_116") (pintype "passive+no_connect"))
    )
    (net (code "96") (name "unconnected-(IC1-LOCK-Pad73)") (class "Default")
      (node (ref "IC1") (pin "73") (pinfunction "LOCK_73") (pintype "passive+no_connect"))
    )
    (net (code "97") (name "unconnected-(IC1-NC-Pad54)") (class "Default")
      (node (ref "IC1") (pin "54") (pinfunction "NC_54") (pintype "passive+no_connect"))
    )
    (net (code "98") (name "unconnected-(IC1-NC-Pad55)") (class "Default")
      (node (ref "IC1") (pin "55") (pinfunction "NC_55") (pintype "passive+no_connect"))
    )
    (net (code "99") (name "unconnected-(IC1-NC-Pad56)") (class "Default")
      (node (ref "IC1") (pin "56") (pinfunction "NC_56") (pintype "passive+no_connect"))
    )
    (net (code "100") (name "unconnected-(IC1-NC-Pad57)") (class "Default")
      (node (ref "IC1") (pin "57") (pinfunction "NC_57") (pintype "passive+no_connect"))
    )
    (net (code "101") (name "unconnected-(IC1-NC-Pad58)") (class "Default")
      (node (ref "IC1") (pin "58") (pinfunction "NC_58") (pintype "passive+no_connect"))
    )
    (net (code "102") (name "unconnected-(IC1-NC-Pad118)") (class "Default")
      (node (ref "IC1") (pin "118") (pinfunction "NC_118") (pintype "passive+no_connect"))
    )
    (net (code "103") (name "unconnected-(IC1-NC-Pad119)") (class "Default")
      (node (ref "IC1") (pin "119") (pinfunction "NC_119") (pintype "passive+no_connect"))
    )
    (net (code "104") (name "unconnected-(IC1-NC-Pad120)") (class "Default")
      (node (ref "IC1") (pin "120") (pinfunction "NC_120") (pintype "passive+no_connect"))
    )
    (net (code "105") (name "unconnected-(IC1-TESTOUT0-Pad133)") (class "Default")
      (node (ref "IC1") (pin "133") (pinfunction "TESTOUT0_133") (pintype "passive+no_connect"))
    )
    (net (code "106") (name "unconnected-(IC1-TESTOUT1-Pad134)") (class "Default")
      (node (ref "IC1") (pin "134") (pinfunction "TESTOUT1_134") (pintype "passive+no_connect"))
    )
    (net (code "107") (name "unconnected-(IC1-TESTOUT2-Pad135)") (class "Default")
      (node (ref "IC1") (pin "135") (pinfunction "TESTOUT2_135") (pintype "passive+no_connect"))
    )
    (net (code "108") (name "unconnected-(IC2-2Q-Pad9)") (class "Default")
      (node (ref "IC2") (pin "9") (pinfunction "2Q_9") (pintype "passive+no_connect"))
    )
    (net (code "109") (name "unconnected-(IC4-2Y-Pad8)") (class "Default")
      (node (ref "IC4") (pin "8") (pinfunction "2Y_8") (pintype "passive+no_connect"))
    )
    (net (code "110") (name "unconnected-(IC4-N.C._1-Pad3)") (class "Default")
      (node (ref "IC4") (pin "3") (pinfunction "N.C._1_3") (pintype "passive+no_connect"))
    )
    (net (code "111") (name "unconnected-(IC4-N.C._2-Pad11)") (class "Default")
      (node (ref "IC4") (pin "11") (pinfunction "N.C._2_11") (pintype "passive+no_connect"))
    )
    (net (code "112") (name "unconnected-(IC5-O1-Pad6)") (class "Default")
      (node (ref "IC5") (pin "6") (pinfunction "O1_6") (pintype "passive+no_connect"))
    )
    (net (code "113") (name "unconnected-(IC5-O2-Pad11)") (class "Default")
      (node (ref "IC5") (pin "11") (pinfunction "O2_11") (pintype "passive+no_connect"))
    )
    (net (code "114") (name "unconnected-(IC5-O3-Pad8)") (class "Default")
      (node (ref "IC5") (pin "8") (pinfunction "O3_8") (pintype "passive+no_connect"))
    )
    (net (code "115") (name "unconnected-(PL1-CPA-Pad76)") (class "Default")
      (node (ref "PL1") (pin "76") (pinfunction "CPA_76") (pintype "passive+no_connect"))
    )
    (net (code "116") (name "unconnected-(PL1-CPB-Pad12)") (class "Default")
      (node (ref "PL1") (pin "12") (pinfunction "CPB_12") (pintype "passive+no_connect"))
    )
    (net (code "117") (name "unconnected-(PL1-PHI1-Pad2)") (class "Default")
      (node (ref "PL1") (pin "2") (pinfunction "PHI1_2") (pintype "passive+no_connect"))
    )
    (net (code "118") (name "unconnected-(PL1-{slash}M0-Pad14)") (class "Default")
      (node (ref "PL1") (pin "14") (pinfunction "/M0_14") (pintype "passive+no_connect"))
    )
    (net (code "119") (name "unconnected-(PL1-{slash}M1-Pad13)") (class "Default")
      (node (ref "PL1") (pin "13") (pinfunction "/M1_13") (pintype "passive+no_connect"))
    )
    (net (code "120") (name "unconnected-(PL1-{slash}OPC-Pad4)") (class "Default")
      (node (ref "PL1") (pin "4") (pinfunction "/OPC_4") (pintype "passive+no_connect"))
    )
    (net (code "121") (name "unconnected-(X1-Pad1)") (class "Default")
      (node (ref "X1") (pin "1") (pinfunction "1_1") (pintype "passive+no_connect"))
    )
    (net (code "122") (name "unconnected-(X2-STANDBY_OPERATION-Pad1)") (class "Default")
      (node (ref "X2") (pin "1") (pinfunction "STANDBY_OPERATION_1") (pintype "passive+no_connect"))
    )
  )
)
